# Detektor_Zic_Detektor_Vlaznosti.net
KiCad netlist of a schematic drawn in Altium Designer
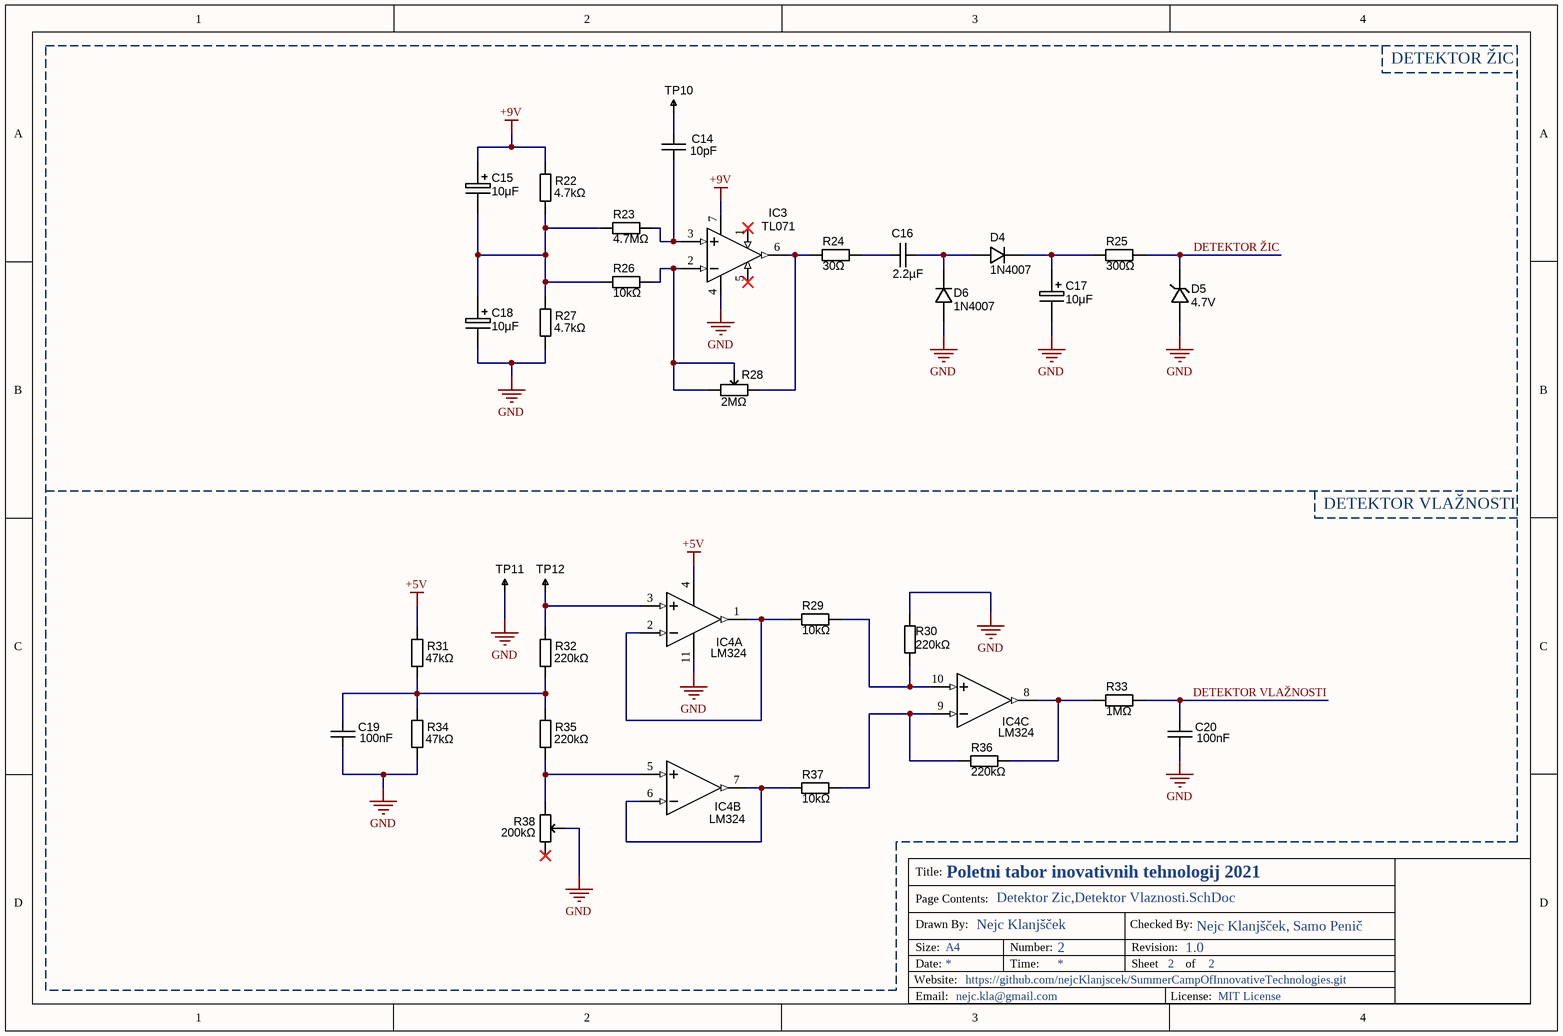
[diagram p0: Detektor Zic,Detektor Vlaznosti.SchDoc]

(export (version "E")
  (design (tool "Eeschema 10.0.6"))
  (components
    (comp (ref "C14")
      (value "10pF")
      (footprint "CAPC500P450250X550")
      (libsource (lib "Nejc Klanjšček") (part "CAPC_2u2_FG28_25V"))
    )
    (comp (ref "C15")
      (value "10μF")
      (footprint "CAPE_5x11x2LS")
      (libsource (lib "Nejc Klanjšček") (part "CAPT_10u_5mm_63V"))
    )
    (comp (ref "C16")
      (value "2.2µF")
      (footprint "CAPC500P450250X550")
      (libsource (lib "Nejc Klanjšček") (part "CAPC_2u2_FG28_25V"))
    )
    (comp (ref "C17")
      (value "10μF")
      (footprint "CAPE_5x11x2LS")
      (libsource (lib "Nejc Klanjšček") (part "CAPT_10u_5mm_63V"))
    )
    (comp (ref "C18")
      (value "10μF")
      (footprint "CAPE_5x11x2LS")
      (libsource (lib "Nejc Klanjšček") (part "CAPT_10u_5mm_63V"))
    )
    (comp (ref "C19")
      (value "100nF")
      (footprint "CAPC500P450250X550")
      (libsource (lib "Nejc Klanjšček") (part "CAPC_2u2_FG28_25V"))
    )
    (comp (ref "C20")
      (value "100nF")
      (footprint "CAPC500P450250X550")
      (libsource (lib "Nejc Klanjšček") (part "CAPC_2u2_FG28_25V"))
    )
    (comp (ref "D4")
      (value "1N4007")
      (footprint "DO-41")
      (description "Diode 1N4007 1A 1000V THD")
      (libsource (lib "Nejc Klanjšček") (part "DIODE_1N4007_1000V_1.0A_DO-41"))
    )
    (comp (ref "D5")
      (value "4.7V")
      (footprint "do-35 - red")
      (description "Diode Zener SMD 4.7V 0.5W SOD-123")
      (fields (field (name "TOLERANCE") "±5%"))
      (libsource (lib "Nejc Klanjšček") (part "BZX79C4V7"))
    )
    (comp (ref "D6")
      (value "1N4007")
      (footprint "DO-41")
      (description "Diode 1N4007 1A 1000V THD")
      (libsource (lib "Nejc Klanjšček") (part "DIODE_1N4007_1000V_1.0A_DO-41"))
    )
    (comp (ref "IC3")
      (value "TL071")
      (footprint "DIP8-300")
      (libsource (lib "Nejc Klanjšček") (part "IC_OP-Amp_TL071"))
    )
    (comp (ref "IC4")
      (value "LM324")
      (footprint "DIP794W66P254L1954H508Q14N")
      (libsource (lib "Nejc Klanjšček") (part "IC_OP-Amp_LM324"))
    )
    (comp (ref "R22")
      (value "4.7kΩ")
      (footprint "RESTH_AXIAL-1/8W")
      (description "Resistor THD Axial 4.7kΩ 0.125W 1% Carbon Film")
      (fields (field (name "TOLERANCE") "±5%") (field (name "Comment") "RES_NL_1/8W"))
      (libsource (lib "") (part "RES_NL_1/8W_1"))
    )
    (comp (ref "R23")
      (value "4.7MΩ")
      (footprint "RESTH_AXIAL-1/8W")
      (description "Resistor THD Axial 4.7MΩ 0.125W 1% Carbon Film")
      (fields (field (name "TOLERANCE") "±5%") (field (name "Comment") "RES_NL_1/8W"))
      (libsource (lib "Nejc Klanjšček") (part "RES_NL_1/8W"))
    )
    (comp (ref "R24")
      (value "30Ω")
      (footprint "RESTH_AXIAL-1/8W")
      (description "Resistor THD Axial 30Ω 0.125W 1% Carbon Film")
      (fields (field (name "TOLERANCE") "±5%") (field (name "Comment") "RES_NL_1/8W"))
      (libsource (lib "Nejc Klanjšček") (part "RES_NL_1/8W"))
    )
    (comp (ref "R25")
      (value "300Ω")
      (footprint "RESTH_AXIAL-1/8W")
      (description "Resistor THD Axial 30Ω 0.125W 1% Carbon Film")
      (fields (field (name "TOLERANCE") "±5%") (field (name "Comment") "RES_NL_1/8W"))
      (libsource (lib "Nejc Klanjšček") (part "RES_NL_1/8W"))
    )
    (comp (ref "R26")
      (value "10kΩ")
      (footprint "RESTH_AXIAL-1/8W")
      (description "Resistor THD Axial 4.7kΩ 0.125W 1% Carbon Film")
      (fields (field (name "TOLERANCE") "±5%") (field (name "Comment") "RES_NL_1/8W"))
      (libsource (lib "Nejc Klanjšček") (part "RES_NL_1/8W"))
    )
    (comp (ref "R27")
      (value "4.7kΩ")
      (footprint "RESTH_AXIAL-1/8W")
      (description "Resistor THD Axial 4.7kΩ 0.125W 1% Carbon Film")
      (fields (field (name "TOLERANCE") "±5%") (field (name "Comment") "RES_NL_1/8W"))
      (libsource (lib "") (part "RES_NL_1/8W_1"))
    )
    (comp (ref "R28")
      (value "2MΩ")
      (footprint "3386F1153")
      (description "Trimmer THD 2MΩ 200mW Single-turn")
      (fields (field (name "TOLERANCE") "±25%") (field (name "Comment") "Single-turn pot"))
      (libsource (lib "Nejc Klanjšček") (part "RES_TRIMMER_2MEG"))
    )
    (comp (ref "R29")
      (value "10kΩ")
      (footprint "RESTH_AXIAL-1/8W")
      (description "Resistor THD Axial 10kΩ 0.125W 1% Carbon Film")
      (fields (field (name "TOLERANCE") "±5%") (field (name "Comment") "RES_NL_1/8W"))
      (libsource (lib "") (part "RES_NL_1/8W_2"))
    )
    (comp (ref "R30")
      (value "220kΩ")
      (footprint "RESTH_AXIAL-1/8W")
      (description "Resistor THD Axial 220kΩ 0.125W 1% Carbon Film")
      (fields (field (name "TOLERANCE") "±5%") (field (name "Comment") "RES_NL_1/8W"))
      (libsource (lib "") (part "RES_NL_1/8W_1"))
    )
    (comp (ref "R31")
      (value "47kΩ")
      (footprint "RESTH_AXIAL-1/8W")
      (description "Resistor THD Axial 47kΩ 0.125W 1% Carbon Film")
      (fields (field (name "TOLERANCE") "±5%") (field (name "Comment") "RES_NL_1/8W"))
      (libsource (lib "") (part "RES_NL_1/8W_1"))
    )
    (comp (ref "R32")
      (value "220kΩ")
      (footprint "RESTH_AXIAL-1/8W")
      (description "Resistor THD Axial 220kΩ 0.125W 1% Carbon Film")
      (fields (field (name "TOLERANCE") "±5%") (field (name "Comment") "RES_NL_1/8W"))
      (libsource (lib "") (part "RES_NL_1/8W_1"))
    )
    (comp (ref "R33")
      (value "1MΩ")
      (footprint "RESTH_AXIAL-1/8W")
      (description "Resistor THD Axial 1MΩ 0.125W 1% Carbon Film")
      (fields (field (name "TOLERANCE") "±5%") (field (name "Comment") "RES_NL_1/8W"))
      (libsource (lib "Nejc Klanjšček") (part "RES_NL_1/8W"))
    )
    (comp (ref "R34")
      (value "47kΩ")
      (footprint "RESTH_AXIAL-1/8W")
      (description "Resistor THD Axial 47kΩ 0.125W 1% Carbon Film")
      (fields (field (name "TOLERANCE") "±5%") (field (name "Comment") "RES_NL_1/8W"))
      (libsource (lib "") (part "RES_NL_1/8W_1"))
    )
    (comp (ref "R35")
      (value "220kΩ")
      (footprint "RESTH_AXIAL-1/8W")
      (description "Resistor THD Axial 220kΩ 0.125W 1% Carbon Film")
      (fields (field (name "TOLERANCE") "±5%") (field (name "Comment") "RES_NL_1/8W"))
      (libsource (lib "") (part "RES_NL_1/8W_1"))
    )
    (comp (ref "R36")
      (value "220kΩ")
      (footprint "RESTH_AXIAL-1/8W")
      (description "Resistor THD Axial 220kΩ 0.125W 1% Carbon Film")
      (fields (field (name "TOLERANCE") "±5%") (field (name "Comment") "RES_NL_1/8W"))
      (libsource (lib "") (part "RES_NL_1/8W_2"))
    )
    (comp (ref "R37")
      (value "10kΩ")
      (footprint "RESTH_AXIAL-1/8W")
      (description "Resistor THD Axial 10kΩ 0.125W 1% Carbon Film")
      (fields (field (name "TOLERANCE") "±5%") (field (name "Comment") "RES_NL_1/8W"))
      (libsource (lib "") (part "RES_NL_1/8W_2"))
    )
    (comp (ref "R38")
      (value "200kΩ")
      (footprint "3386P1103TLF")
      (description "Trimmer THD 10K 200mW Single-turn")
      (fields (field (name "TOLERANCE") "±25%") (field (name "Comment") "Single-turn pot"))
      (libsource (lib "Nejc Klanjšček") (part "RES_TRIMMER_200k"))
    )
    (comp (ref "TP10")
      (value "TESTPOINT_THT")
      (footprint "TP-THT-MULTI")
      (description "Test Point PCB mount Multi-purpose Yellow")
      (libsource (lib "Nejc Klanjšček") (part "TESTPOINT_THT"))
    )
    (comp (ref "TP11")
      (value "TESTPOINT_THT")
      (footprint "TP-THT-MULTI")
      (description "Test Point PCB mount Multi-purpose Yellow")
      (libsource (lib "Nejc Klanjšček") (part "TESTPOINT_THT"))
    )
    (comp (ref "TP12")
      (value "TESTPOINT_THT")
      (footprint "TP-THT-MULTI")
      (description "Test Point PCB mount Multi-purpose Yellow")
      (libsource (lib "Nejc Klanjšček") (part "TESTPOINT_THT"))
    )
  )
  (nets
    (net (code "1") (name "+5V") (class "Default")
      (node (ref "IC4") (pin "4") (pinfunction "V+_4") (pintype "power_in"))
      (node (ref "R31") (pin "1") (pinfunction "1_1") (pintype "passive"))
    )
    (net (code "2") (name "+9V") (class "Default")
      (node (ref "C15") (pin "1") (pintype "passive"))
      (node (ref "IC3") (pin "7") (pinfunction "+Vs_7") (pintype "power_in"))
      (node (ref "R22") (pin "1") (pinfunction "1_1") (pintype "passive"))
    )
    (net (code "3") (name "/DETEKTOR VLAŽNOSTI") (class "Default")
      (node (ref "C20") (pin "1") (pintype "passive"))
      (node (ref "R33") (pin "2") (pinfunction "2_2") (pintype "passive"))
    )
    (net (code "4") (name "/DETEKTOR ŽIC") (class "Default")
      (node (ref "D5") (pin "K") (pinfunction "K_K") (pintype "passive"))
      (node (ref "R25") (pin "2") (pinfunction "2_2") (pintype "passive"))
    )
    (net (code "5") (name "GND") (class "Default")
      (node (ref "C17") (pin "2") (pintype "passive"))
      (node (ref "C18") (pin "2") (pintype "passive"))
      (node (ref "C19") (pin "2") (pintype "passive"))
      (node (ref "C20") (pin "2") (pintype "passive"))
      (node (ref "D5") (pin "A") (pinfunction "A_A") (pintype "passive"))
      (node (ref "D6") (pin "A") (pinfunction "A_A") (pintype "passive"))
      (node (ref "IC3") (pin "4") (pinfunction "-Vs_4") (pintype "power_in"))
      (node (ref "IC4") (pin "11") (pinfunction "V-_11") (pintype "power_in"))
      (node (ref "R27") (pin "2") (pinfunction "2_2") (pintype "passive"))
      (node (ref "R30") (pin "1") (pinfunction "1_1") (pintype "passive"))
      (node (ref "R34") (pin "2") (pinfunction "2_2") (pintype "passive"))
      (node (ref "R38") (pin "2") (pinfunction "W_2") (pintype "passive"))
      (node (ref "TP11") (pin "1") (pintype "passive"))
    )
    (net (code "6") (name "Net-(C14-Pad2)") (class "Default")
      (node (ref "C14") (pin "2") (pintype "passive"))
      (node (ref "TP10") (pin "1") (pintype "passive"))
    )
    (net (code "7") (name "Net-(C15-Pad2)") (class "Default")
      (node (ref "C15") (pin "2") (pintype "passive"))
      (node (ref "C18") (pin "1") (pintype "passive"))
      (node (ref "R22") (pin "2") (pinfunction "2_2") (pintype "passive"))
      (node (ref "R23") (pin "1") (pinfunction "1_1") (pintype "passive"))
      (node (ref "R26") (pin "1") (pinfunction "1_1") (pintype "passive"))
      (node (ref "R27") (pin "1") (pinfunction "1_1") (pintype "passive"))
    )
    (net (code "8") (name "Net-(C16-Pad1)") (class "Default")
      (node (ref "C16") (pin "1") (pintype "passive"))
      (node (ref "R24") (pin "2") (pinfunction "2_2") (pintype "passive"))
    )
    (net (code "9") (name "Net-(C16-Pad2)") (class "Default")
      (node (ref "C16") (pin "2") (pintype "passive"))
      (node (ref "D4") (pin "A") (pinfunction "A_A") (pintype "passive"))
      (node (ref "D6") (pin "K") (pinfunction "K_K") (pintype "passive"))
    )
    (net (code "10") (name "Net-(C17-Pad1)") (class "Default")
      (node (ref "C17") (pin "1") (pintype "passive"))
      (node (ref "D4") (pin "K") (pinfunction "K_K") (pintype "passive"))
      (node (ref "R25") (pin "1") (pinfunction "1_1") (pintype "passive"))
    )
    (net (code "11") (name "Net-(C19-Pad1)") (class "Default")
      (node (ref "C19") (pin "1") (pintype "passive"))
      (node (ref "R31") (pin "2") (pinfunction "2_2") (pintype "passive"))
      (node (ref "R32") (pin "2") (pinfunction "2_2") (pintype "passive"))
      (node (ref "R34") (pin "1") (pinfunction "1_1") (pintype "passive"))
      (node (ref "R35") (pin "1") (pinfunction "1_1") (pintype "passive"))
    )
    (net (code "12") (name "Net-(IC3-+IN)") (class "Default")
      (node (ref "C14") (pin "1") (pintype "passive"))
      (node (ref "IC3") (pin "3") (pinfunction "+IN_3") (pintype "input"))
      (node (ref "R23") (pin "2") (pinfunction "2_2") (pintype "passive"))
    )
    (net (code "13") (name "Net-(IC3--IN)") (class "Default")
      (node (ref "IC3") (pin "2") (pinfunction "-IN_2") (pintype "input"))
      (node (ref "R26") (pin "2") (pinfunction "2_2") (pintype "passive"))
      (node (ref "R28") (pin "2") (pinfunction "W_2") (pintype "passive"))
      (node (ref "R28") (pin "3") (pinfunction "CW_3") (pintype "passive"))
    )
    (net (code "14") (name "Net-(IC3-OUT)") (class "Default")
      (node (ref "IC3") (pin "6") (pinfunction "OUT_6") (pintype "output"))
      (node (ref "R24") (pin "1") (pinfunction "1_1") (pintype "passive"))
      (node (ref "R28") (pin "1") (pinfunction "CCW_1") (pintype "passive"))
    )
    (net (code "15") (name "Net-(IC4A-IN+)") (class "Default")
      (node (ref "IC4") (pin "3") (pinfunction "IN+_3") (pintype "input"))
      (node (ref "R32") (pin "1") (pinfunction "1_1") (pintype "passive"))
      (node (ref "TP12") (pin "1") (pintype "passive"))
    )
    (net (code "16") (name "Net-(IC4A-IN-)") (class "Default")
      (node (ref "IC4") (pin "1") (pinfunction "OUT_1") (pintype "output"))
      (node (ref "IC4") (pin "2") (pinfunction "IN-_2") (pintype "input"))
      (node (ref "R29") (pin "2") (pinfunction "2_2") (pintype "passive"))
    )
    (net (code "17") (name "Net-(IC4B-IN+)") (class "Default")
      (node (ref "IC4") (pin "5") (pinfunction "IN+_5") (pintype "input"))
      (node (ref "R35") (pin "2") (pinfunction "2_2") (pintype "passive"))
      (node (ref "R38") (pin "3") (pinfunction "CW_3") (pintype "passive"))
    )
    (net (code "18") (name "Net-(IC4B-IN-)") (class "Default")
      (node (ref "IC4") (pin "6") (pinfunction "IN-_6") (pintype "input"))
      (node (ref "IC4") (pin "7") (pinfunction "OUT_7") (pintype "output"))
      (node (ref "R37") (pin "2") (pinfunction "2_2") (pintype "passive"))
    )
    (net (code "19") (name "Net-(IC4C-IN+)") (class "Default")
      (node (ref "IC4") (pin "10") (pinfunction "IN+_10") (pintype "input"))
      (node (ref "R29") (pin "1") (pinfunction "1_1") (pintype "passive"))
      (node (ref "R30") (pin "2") (pinfunction "2_2") (pintype "passive"))
    )
    (net (code "20") (name "Net-(IC4C-IN-)") (class "Default")
      (node (ref "IC4") (pin "9") (pinfunction "IN-_9") (pintype "input"))
      (node (ref "R36") (pin "2") (pinfunction "2_2") (pintype "passive"))
      (node (ref "R37") (pin "1") (pinfunction "1_1") (pintype "passive"))
    )
    (net (code "21") (name "Net-(IC4C-OUT)") (class "Default")
      (node (ref "IC4") (pin "8") (pinfunction "OUT_8") (pintype "output"))
      (node (ref "R33") (pin "1") (pinfunction "1_1") (pintype "passive"))
      (node (ref "R36") (pin "1") (pinfunction "1_1") (pintype "passive"))
    )
    (net (code "22") (name "unconnected-(IC3-Latch-Pad5)") (class "Default")
      (node (ref "IC3") (pin "5") (pinfunction "Latch_5") (pintype "input+no_connect"))
    )
    (net (code "23") (name "unconnected-(IC3-Vlogic-Pad1)") (class "Default")
      (node (ref "IC3") (pin "1") (pinfunction "Vlogic_1") (pintype "input+no_connect"))
    )
    (net (code "24") (name "unconnected-(R38-CCW-Pad1)") (class "Default")
      (node (ref "R38") (pin "1") (pinfunction "CCW_1") (pintype "passive+no_connect"))
    )
  )
)
